# 11_iMX_8X_SPI_ADC.net
KiCad netlist of a schematic drawn in Altium Designer
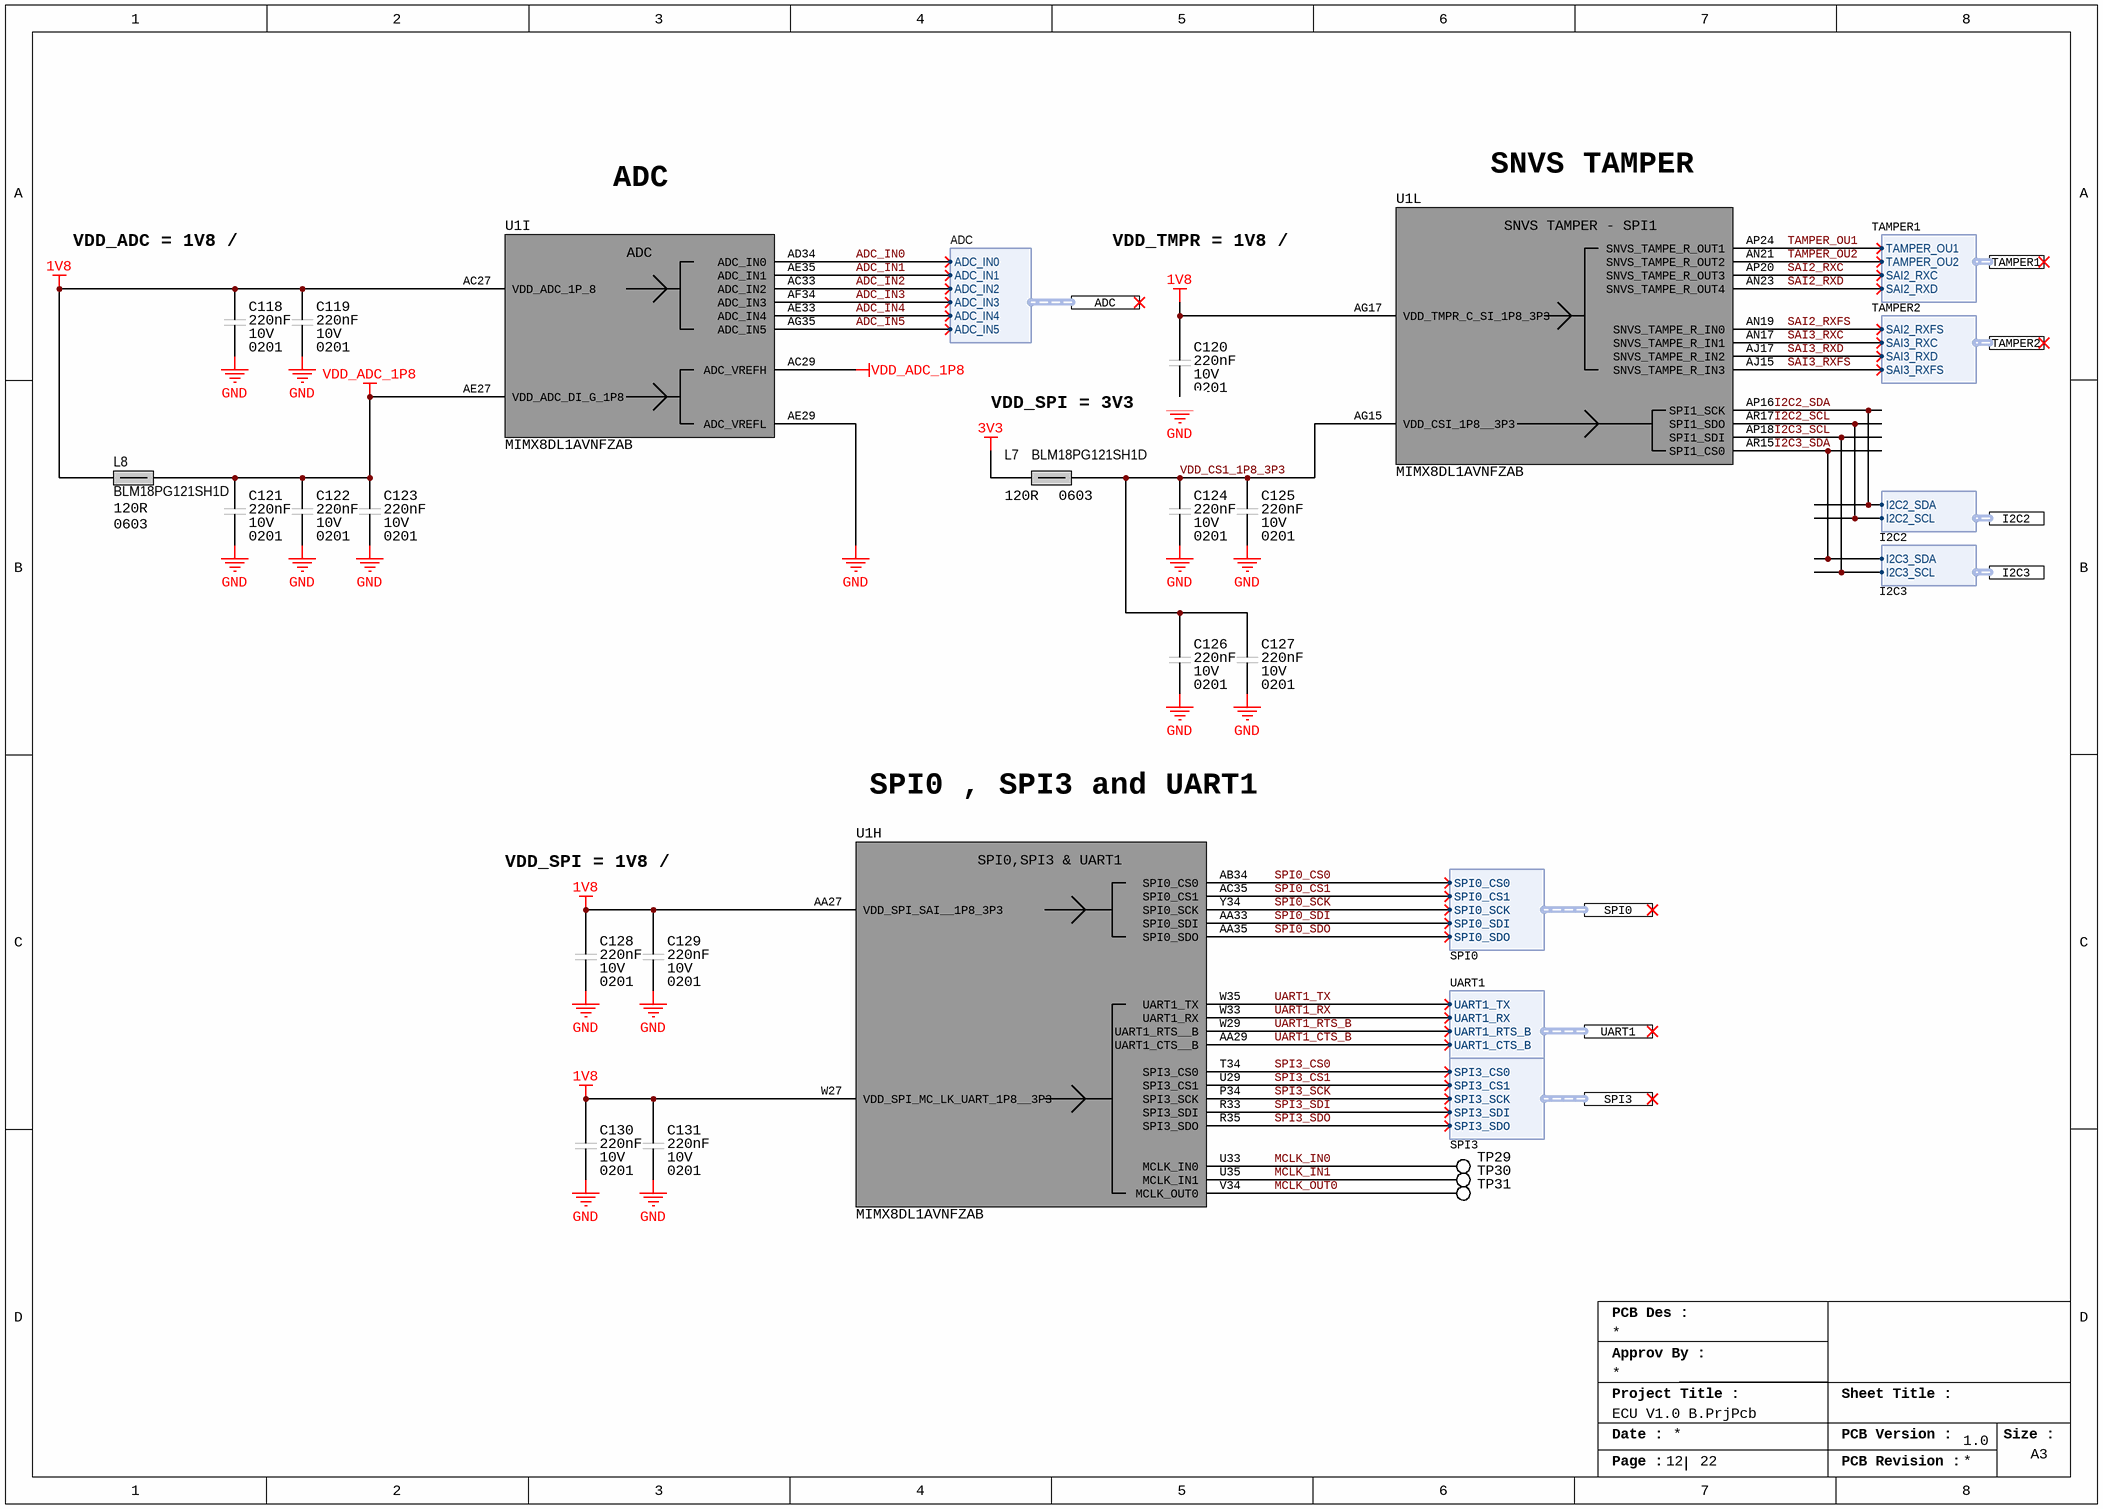
[diagram p0: 11_iMX 8X_SPI & ADC.SchDoc]

(export (version "E")
  (design (tool "Eeschema 10.0.6"))
  (components
    (comp (ref "C118")
      (value "LMK063BJ224MP-F")
      (footprint "CAP_0201_CAPC0603X03N")
      (description "Multilayer Ceramic Capacitors (High dielectric type), 10V, 0.22 uF, ± 20 %, 0201, X5R, RoHS")
      (fields
        (field (name "MANUFACTURER") "Taiyo Yuden")
        (field (name "TOLERANCE") "20%")
        (field (name "VOLTAGE RATING (DC)") "10V")
        (field (name "CAPACITANCE") "220nF")
        (field (name "CASE/PACKAGE") "0201")
      )
      (libsource (lib "Electronic Devices_LIB") (part "CAP_0.22UF_10V_X5R_0201"))
    )
    (comp (ref "C119")
      (value "LMK063BJ224MP-F")
      (footprint "CAP_0201_CAPC0603X03N")
      (description "Multilayer Ceramic Capacitors (High dielectric type), 10V, 0.22 uF, ± 20 %, 0201, X5R, RoHS")
      (fields
        (field (name "MANUFACTURER") "Taiyo Yuden")
        (field (name "TOLERANCE") "20%")
        (field (name "VOLTAGE RATING (DC)") "10V")
        (field (name "CAPACITANCE") "220nF")
        (field (name "CASE/PACKAGE") "0201")
      )
      (libsource (lib "Electronic Devices_LIB") (part "CAP_0.22UF_10V_X5R_0201"))
    )
    (comp (ref "C120")
      (value "LMK063BJ224MP-F")
      (footprint "CAP_0201_CAPC0603X03N")
      (description "Multilayer Ceramic Capacitors (High dielectric type), 10V, 0.22 uF, ± 20 %, 0201, X5R, RoHS")
      (fields
        (field (name "MANUFACTURER") "Taiyo Yuden")
        (field (name "TOLERANCE") "20%")
        (field (name "VOLTAGE RATING (DC)") "10V")
        (field (name "CAPACITANCE") "220nF")
        (field (name "CASE/PACKAGE") "0201")
      )
      (libsource (lib "Electronic Devices_LIB") (part "CAP_0.22UF_10V_X5R_0201"))
    )
    (comp (ref "C121")
      (value "LMK063BJ224MP-F")
      (footprint "CAP_0201_CAPC0603X03N")
      (description "Multilayer Ceramic Capacitors (High dielectric type), 10V, 0.22 uF, ± 20 %, 0201, X5R, RoHS")
      (fields
        (field (name "MANUFACTURER") "Taiyo Yuden")
        (field (name "TOLERANCE") "20%")
        (field (name "VOLTAGE RATING (DC)") "10V")
        (field (name "CAPACITANCE") "220nF")
        (field (name "CASE/PACKAGE") "0201")
      )
      (libsource (lib "Electronic Devices_LIB") (part "CAP_0.22UF_10V_X5R_0201"))
    )
    (comp (ref "C122")
      (value "LMK063BJ224MP-F")
      (footprint "CAP_0201_CAPC0603X03N")
      (description "Multilayer Ceramic Capacitors (High dielectric type), 10V, 0.22 uF, ± 20 %, 0201, X5R, RoHS")
      (fields
        (field (name "MANUFACTURER") "Taiyo Yuden")
        (field (name "TOLERANCE") "20%")
        (field (name "VOLTAGE RATING (DC)") "10V")
        (field (name "CAPACITANCE") "220nF")
        (field (name "CASE/PACKAGE") "0201")
      )
      (libsource (lib "Electronic Devices_LIB") (part "CAP_0.22UF_10V_X5R_0201"))
    )
    (comp (ref "C123")
      (value "LMK063BJ224MP-F")
      (footprint "CAP_0201_CAPC0603X03N")
      (description "Multilayer Ceramic Capacitors (High dielectric type), 10V, 0.22 uF, ± 20 %, 0201, X5R, RoHS")
      (fields
        (field (name "MANUFACTURER") "Taiyo Yuden")
        (field (name "TOLERANCE") "20%")
        (field (name "VOLTAGE RATING (DC)") "10V")
        (field (name "CAPACITANCE") "220nF")
        (field (name "CASE/PACKAGE") "0201")
      )
      (libsource (lib "Electronic Devices_LIB") (part "CAP_0.22UF_10V_X5R_0201"))
    )
    (comp (ref "C124")
      (value "LMK063BJ224MP-F")
      (footprint "CAP_0201_CAPC0603X03N")
      (description "Multilayer Ceramic Capacitors (High dielectric type), 10V, 0.22 uF, ± 20 %, 0201, X5R, RoHS")
      (fields
        (field (name "MANUFACTURER") "Taiyo Yuden")
        (field (name "TOLERANCE") "20%")
        (field (name "VOLTAGE RATING (DC)") "10V")
        (field (name "CAPACITANCE") "220nF")
        (field (name "CASE/PACKAGE") "0201")
      )
      (libsource (lib "Electronic Devices_LIB") (part "CAP_0.22UF_10V_X5R_0201"))
    )
    (comp (ref "C125")
      (value "LMK063BJ224MP-F")
      (footprint "CAP_0201_CAPC0603X03N")
      (description "Multilayer Ceramic Capacitors (High dielectric type), 10V, 0.22 uF, ± 20 %, 0201, X5R, RoHS")
      (fields
        (field (name "MANUFACTURER") "Taiyo Yuden")
        (field (name "TOLERANCE") "20%")
        (field (name "VOLTAGE RATING (DC)") "10V")
        (field (name "CAPACITANCE") "220nF")
        (field (name "CASE/PACKAGE") "0201")
      )
      (libsource (lib "Electronic Devices_LIB") (part "CAP_0.22UF_10V_X5R_0201"))
    )
    (comp (ref "C126")
      (value "LMK063BJ224MP-F")
      (footprint "CAP_0201_CAPC0603X03N")
      (description "Multilayer Ceramic Capacitors (High dielectric type), 10V, 0.22 uF, ± 20 %, 0201, X5R, RoHS")
      (fields
        (field (name "MANUFACTURER") "Taiyo Yuden")
        (field (name "TOLERANCE") "20%")
        (field (name "VOLTAGE RATING (DC)") "10V")
        (field (name "CAPACITANCE") "220nF")
        (field (name "CASE/PACKAGE") "0201")
      )
      (libsource (lib "Electronic Devices_LIB") (part "CAP_0.22UF_10V_X5R_0201"))
    )
    (comp (ref "C127")
      (value "LMK063BJ224MP-F")
      (footprint "CAP_0201_CAPC0603X03N")
      (description "Multilayer Ceramic Capacitors (High dielectric type), 10V, 0.22 uF, ± 20 %, 0201, X5R, RoHS")
      (fields
        (field (name "MANUFACTURER") "Taiyo Yuden")
        (field (name "TOLERANCE") "20%")
        (field (name "VOLTAGE RATING (DC)") "10V")
        (field (name "CAPACITANCE") "220nF")
        (field (name "CASE/PACKAGE") "0201")
      )
      (libsource (lib "Electronic Devices_LIB") (part "CAP_0.22UF_10V_X5R_0201"))
    )
    (comp (ref "C128")
      (value "LMK063BJ224MP-F")
      (footprint "CAP_0201_CAPC0603X03N")
      (description "Multilayer Ceramic Capacitors (High dielectric type), 10V, 0.22 uF, ± 20 %, 0201, X5R, RoHS")
      (fields
        (field (name "MANUFACTURER") "Taiyo Yuden")
        (field (name "TOLERANCE") "20%")
        (field (name "VOLTAGE RATING (DC)") "10V")
        (field (name "CAPACITANCE") "220nF")
        (field (name "CASE/PACKAGE") "0201")
      )
      (libsource (lib "Electronic Devices_LIB") (part "CAP_0.22UF_10V_X5R_0201"))
    )
    (comp (ref "C129")
      (value "LMK063BJ224MP-F")
      (footprint "CAP_0201_CAPC0603X03N")
      (description "Multilayer Ceramic Capacitors (High dielectric type), 10V, 0.22 uF, ± 20 %, 0201, X5R, RoHS")
      (fields
        (field (name "MANUFACTURER") "Taiyo Yuden")
        (field (name "TOLERANCE") "20%")
        (field (name "VOLTAGE RATING (DC)") "10V")
        (field (name "CAPACITANCE") "220nF")
        (field (name "CASE/PACKAGE") "0201")
      )
      (libsource (lib "Electronic Devices_LIB") (part "CAP_0.22UF_10V_X5R_0201"))
    )
    (comp (ref "C130")
      (value "LMK063BJ224MP-F")
      (footprint "CAP_0201_CAPC0603X03N")
      (description "Multilayer Ceramic Capacitors (High dielectric type), 10V, 0.22 uF, ± 20 %, 0201, X5R, RoHS")
      (fields
        (field (name "MANUFACTURER") "Taiyo Yuden")
        (field (name "TOLERANCE") "20%")
        (field (name "VOLTAGE RATING (DC)") "10V")
        (field (name "CAPACITANCE") "220nF")
        (field (name "CASE/PACKAGE") "0201")
      )
      (libsource (lib "Electronic Devices_LIB") (part "CAP_0.22UF_10V_X5R_0201"))
    )
    (comp (ref "C131")
      (value "LMK063BJ224MP-F")
      (footprint "CAP_0201_CAPC0603X03N")
      (description "Multilayer Ceramic Capacitors (High dielectric type), 10V, 0.22 uF, ± 20 %, 0201, X5R, RoHS")
      (fields
        (field (name "MANUFACTURER") "Taiyo Yuden")
        (field (name "TOLERANCE") "20%")
        (field (name "VOLTAGE RATING (DC)") "10V")
        (field (name "CAPACITANCE") "220nF")
        (field (name "CASE/PACKAGE") "0201")
      )
      (libsource (lib "Electronic Devices_LIB") (part "CAP_0.22UF_10V_X5R_0201"))
    )
    (comp (ref "L7")
      (value "BLM18PG121SH1D")
      (footprint "IND_0603_INDC1608X08N")
      (description "Ferrite Beads Multi-Layer 120Ohm 25% 100MHz 2A 50mOhm DCR 0603 Automotive Paper T/R")
      (fields
        (field (name "MANUFACTURER") "Murata")
        (field (name "TOLERANCE") "25%")
        (field (name "IMPEDANCE") "120R")
        (field (name "CASE/PACKAGE") "0603")
      )
      (libsource (lib "Electronic Devices_LIB") (part "IND_FERRITE_BEADS_120R_2A_0603_BLM18PG121SH1D"))
    )
    (comp (ref "L8")
      (value "BLM18PG121SH1D")
      (footprint "IND_0603_INDC1608X08N")
      (description "Ferrite Beads Multi-Layer 120Ohm 25% 100MHz 2A 50mOhm DCR 0603 Automotive Paper T/R")
      (fields
        (field (name "MANUFACTURER") "Murata")
        (field (name "TOLERANCE") "25%")
        (field (name "IMPEDANCE") "120R")
        (field (name "CASE/PACKAGE") "0603")
      )
      (libsource (lib "Electronic Devices_LIB") (part "IND_FERRITE_BEADS_120R_2A_0603_BLM18PG121SH1D"))
    )
    (comp (ref "TP29")
      (value "NO COMPONENT")
      (footprint "TP_PAD_0.5MM_SMD_ROUND")
      (description "Test Point, SMD pad, round, 1.5mm, 1.6mm, 3mm diameter")
      (libsource (lib "Electronic Devices_LIB") (part "TP_PAD_SMD_SMALL"))
    )
    (comp (ref "TP30")
      (value "NO COMPONENT")
      (footprint "TP_PAD_0.5MM_SMD_ROUND")
      (description "Test Point, SMD pad, round, 1.5mm, 1.6mm, 3mm diameter")
      (libsource (lib "Electronic Devices_LIB") (part "TP_PAD_SMD_SMALL"))
    )
    (comp (ref "TP31")
      (value "NO COMPONENT")
      (footprint "TP_PAD_0.5MM_SMD_ROUND")
      (description "Test Point, SMD pad, round, 1.5mm, 1.6mm, 3mm diameter")
      (libsource (lib "Electronic Devices_LIB") (part "TP_PAD_SMD_SMALL"))
    )
    (comp (ref "U1")
      (value "MIMX8DL1AVNFZAB")
      (footprint "MIMX8DL1AVNFZAB")
      (description "I.MX8 Dxl 15SQ / Tray Rohs Compliant: Yes")
      (fields (field (name "MANUFACTURER") "NXP Semiconductors"))
      (libsource (lib "Electronic Devices_LIB") (part "IC_MPU_ARM_1.2GHz_MIMX8DL1AVNFZAB"))
    )
  )
  (nets
    (net (code "9") (name "/ADC_IN0") (class "Default")
      (node (ref "U1") (pin "AD34") (pinfunction "ADC_IN0_AD34") (pintype "passive+no_connect"))
    )
    (net (code "10") (name "/ADC_IN1") (class "Default")
      (node (ref "U1") (pin "AE35") (pinfunction "ADC_IN1_AE35") (pintype "passive+no_connect"))
    )
    (net (code "11") (name "/ADC_IN2") (class "Default")
      (node (ref "U1") (pin "AC33") (pinfunction "ADC_IN2_AC33") (pintype "passive+no_connect"))
    )
    (net (code "12") (name "/ADC_IN3") (class "Default")
      (node (ref "U1") (pin "AF34") (pinfunction "ADC_IN3_AF34") (pintype "passive+no_connect"))
    )
    (net (code "13") (name "/ADC_IN4") (class "Default")
      (node (ref "U1") (pin "AE33") (pinfunction "ADC_IN4_AE33") (pintype "passive+no_connect"))
    )
    (net (code "14") (name "/ADC_IN5") (class "Default")
      (node (ref "U1") (pin "AG35") (pinfunction "ADC_IN5_AG35") (pintype "passive+no_connect"))
    )
    (net (code "15") (name "/I2C2_SCL") (class "Default")
      (node (ref "U1") (pin "AR17") (pinfunction "SPI1_SDO_AR17") (pintype "passive"))
    )
    (net (code "16") (name "/I2C2_SDA") (class "Default")
      (node (ref "U1") (pin "AP16") (pinfunction "SPI1_SCK_AP16") (pintype "passive"))
    )
    (net (code "17") (name "/I2C3_SCL") (class "Default")
      (node (ref "U1") (pin "AP18") (pinfunction "SPI1_SDI_AP18") (pintype "passive"))
    )
    (net (code "18") (name "/I2C3_SDA") (class "Default")
      (node (ref "U1") (pin "AR15") (pinfunction "SPI1_CS0_AR15") (pintype "passive"))
    )
    (net (code "19") (name "/MCLK_IN0") (class "Default")
      (node (ref "TP29") (pin "1") (pinfunction "1_1") (pintype "passive"))
      (node (ref "U1") (pin "U33") (pinfunction "MCLK_IN0_U33") (pintype "passive"))
    )
    (net (code "20") (name "/MCLK_IN1") (class "Default")
      (node (ref "TP30") (pin "1") (pinfunction "1_1") (pintype "passive"))
      (node (ref "U1") (pin "U35") (pinfunction "MCLK_IN1_U35") (pintype "passive"))
    )
    (net (code "21") (name "/MCLK_OUT0") (class "Default")
      (node (ref "TP31") (pin "1") (pinfunction "1_1") (pintype "passive"))
      (node (ref "U1") (pin "V34") (pinfunction "MCLK_OUT0_V34") (pintype "passive"))
    )
    (net (code "22") (name "/SAI2_RXC") (class "Default")
      (node (ref "U1") (pin "AP20") (pinfunction "SNVS_TAMPE_R_OUT3_AP20") (pintype "passive+no_connect"))
    )
    (net (code "23") (name "/SAI2_RXD") (class "Default")
      (node (ref "U1") (pin "AN23") (pinfunction "SNVS_TAMPE_R_OUT4_AN23") (pintype "passive+no_connect"))
    )
    (net (code "24") (name "/SAI2_RXFS") (class "Default")
      (node (ref "U1") (pin "AN19") (pinfunction "SNVS_TAMPE_R_IN0_AN19") (pintype "passive+no_connect"))
    )
    (net (code "25") (name "/SAI3_RXC") (class "Default")
      (node (ref "U1") (pin "AN17") (pinfunction "SNVS_TAMPE_R_IN1_AN17") (pintype "passive+no_connect"))
    )
    (net (code "26") (name "/SAI3_RXD") (class "Default")
      (node (ref "U1") (pin "AJ17") (pinfunction "SNVS_TAMPE_R_IN2_AJ17") (pintype "passive+no_connect"))
    )
    (net (code "27") (name "/SAI3_RXFS") (class "Default")
      (node (ref "U1") (pin "AJ15") (pinfunction "SNVS_TAMPE_R_IN3_AJ15") (pintype "passive+no_connect"))
    )
    (net (code "28") (name "/SPI0_CS0") (class "Default")
      (node (ref "U1") (pin "AB34") (pinfunction "SPI0_CS0_AB34") (pintype "passive+no_connect"))
    )
    (net (code "29") (name "/SPI0_CS1") (class "Default")
      (node (ref "U1") (pin "AC35") (pinfunction "SPI0_CS1_AC35") (pintype "passive+no_connect"))
    )
    (net (code "30") (name "/SPI0_SCK") (class "Default")
      (node (ref "U1") (pin "Y34") (pinfunction "SPI0_SCK_Y34") (pintype "passive+no_connect"))
    )
    (net (code "31") (name "/SPI0_SDI") (class "Default")
      (node (ref "U1") (pin "AA33") (pinfunction "SPI0_SDI_AA33") (pintype "passive+no_connect"))
    )
    (net (code "32") (name "/SPI0_SDO") (class "Default")
      (node (ref "U1") (pin "AA35") (pinfunction "SPI0_SDO_AA35") (pintype "passive+no_connect"))
    )
    (net (code "33") (name "/SPI3_CS0") (class "Default")
      (node (ref "U1") (pin "T34") (pinfunction "SPI3_CS0_T34") (pintype "passive+no_connect"))
    )
    (net (code "34") (name "/SPI3_CS1") (class "Default")
      (node (ref "U1") (pin "U29") (pinfunction "SPI3_CS1_U29") (pintype "passive+no_connect"))
    )
    (net (code "35") (name "/SPI3_SCK") (class "Default")
      (node (ref "U1") (pin "P34") (pinfunction "SPI3_SCK_P34") (pintype "passive+no_connect"))
    )
    (net (code "36") (name "/SPI3_SDI") (class "Default")
      (node (ref "U1") (pin "R33") (pinfunction "SPI3_SDI_R33") (pintype "passive+no_connect"))
    )
    (net (code "37") (name "/SPI3_SDO") (class "Default")
      (node (ref "U1") (pin "R35") (pinfunction "SPI3_SDO_R35") (pintype "passive+no_connect"))
    )
    (net (code "38") (name "/TAMPER_OU1") (class "Default")
      (node (ref "U1") (pin "AP24") (pinfunction "SNVS_TAMPE_R_OUT1_AP24") (pintype "passive+no_connect"))
    )
    (net (code "39") (name "/TAMPER_OU2") (class "Default")
      (node (ref "U1") (pin "AN21") (pinfunction "SNVS_TAMPE_R_OUT2_AN21") (pintype "passive+no_connect"))
    )
    (net (code "40") (name "/UART1_CTS_B") (class "Default")
      (node (ref "U1") (pin "AA29") (pinfunction "UART1_CTS__B_AA29") (pintype "passive+no_connect"))
    )
    (net (code "41") (name "/UART1_RTS_B") (class "Default")
      (node (ref "U1") (pin "W29") (pinfunction "UART1_RTS__B_W29") (pintype "passive+no_connect"))
    )
    (net (code "42") (name "/UART1_RX") (class "Default")
      (node (ref "U1") (pin "W33") (pinfunction "UART1_RX_W33") (pintype "passive+no_connect"))
    )
    (net (code "43") (name "/UART1_TX") (class "Default")
      (node (ref "U1") (pin "W35") (pinfunction "UART1_TX_W35") (pintype "passive+no_connect"))
    )
    (net (code "45") (name "/VDD_CS1_1P8_3P3") (class "Default")
      (node (ref "C124") (pin "2") (pinfunction "2_2") (pintype "passive"))
      (node (ref "C125") (pin "2") (pinfunction "2_2") (pintype "passive"))
      (node (ref "C126") (pin "2") (pinfunction "2_2") (pintype "passive"))
      (node (ref "C127") (pin "2") (pinfunction "2_2") (pintype "passive"))
      (node (ref "L7") (pin "2") (pinfunction "2_2") (pintype "passive"))
      (node (ref "U1") (pin "AG15") (pinfunction "VDD_CSI_1P8__3P3_AG15") (pintype "passive"))
    )
    (net (code "53") (name "1V8") (class "Default")
      (node (ref "C118") (pin "2") (pinfunction "2_2") (pintype "passive"))
      (node (ref "C119") (pin "2") (pinfunction "2_2") (pintype "passive"))
      (node (ref "C120") (pin "2") (pinfunction "2_2") (pintype "passive"))
      (node (ref "C128") (pin "2") (pinfunction "2_2") (pintype "passive"))
      (node (ref "C129") (pin "2") (pinfunction "2_2") (pintype "passive"))
      (node (ref "C130") (pin "2") (pinfunction "2_2") (pintype "passive"))
      (node (ref "C131") (pin "2") (pinfunction "2_2") (pintype "passive"))
      (node (ref "L8") (pin "1") (pinfunction "1_1") (pintype "passive"))
      (node (ref "U1") (pin "AA27") (pinfunction "VDD_SPI_SAI__1P8_3P3_AA27") (pintype "passive"))
      (node (ref "U1") (pin "AC27") (pinfunction "VDD_ADC_1P_8_AC27") (pintype "passive"))
      (node (ref "U1") (pin "AG17") (pinfunction "VDD_TMPR_C_SI_1P8_3P3_AG17") (pintype "passive"))
      (node (ref "U1") (pin "W27") (pinfunction "VDD_SPI_MC_LK_UART_1P8__3P3_W27") (pintype "passive"))
    )
    (net (code "54") (name "3V3") (class "Default")
      (node (ref "L7") (pin "1") (pinfunction "1_1") (pintype "passive"))
    )
    (net (code "55") (name "GND") (class "Default")
      (node (ref "C118") (pin "1") (pinfunction "1_1") (pintype "passive"))
      (node (ref "C119") (pin "1") (pinfunction "1_1") (pintype "passive"))
      (node (ref "C120") (pin "1") (pinfunction "1_1") (pintype "passive"))
      (node (ref "C121") (pin "1") (pinfunction "1_1") (pintype "passive"))
      (node (ref "C122") (pin "1") (pinfunction "1_1") (pintype "passive"))
      (node (ref "C123") (pin "1") (pinfunction "1_1") (pintype "passive"))
      (node (ref "C124") (pin "1") (pinfunction "1_1") (pintype "passive"))
      (node (ref "C125") (pin "1") (pinfunction "1_1") (pintype "passive"))
      (node (ref "C126") (pin "1") (pinfunction "1_1") (pintype "passive"))
      (node (ref "C127") (pin "1") (pinfunction "1_1") (pintype "passive"))
      (node (ref "C128") (pin "1") (pinfunction "1_1") (pintype "passive"))
      (node (ref "C129") (pin "1") (pinfunction "1_1") (pintype "passive"))
      (node (ref "C130") (pin "1") (pinfunction "1_1") (pintype "passive"))
      (node (ref "C131") (pin "1") (pinfunction "1_1") (pintype "passive"))
      (node (ref "U1") (pin "AE29") (pinfunction "ADC_VREFL_AE29") (pintype "passive"))
    )
    (net (code "56") (name "VDD_ADC_1P8") (class "Default")
      (node (ref "C121") (pin "2") (pinfunction "2_2") (pintype "passive"))
      (node (ref "C122") (pin "2") (pinfunction "2_2") (pintype "passive"))
      (node (ref "C123") (pin "2") (pinfunction "2_2") (pintype "passive"))
      (node (ref "L8") (pin "2") (pinfunction "2_2") (pintype "passive"))
      (node (ref "U1") (pin "AC29") (pinfunction "ADC_VREFH_AC29") (pintype "passive"))
      (node (ref "U1") (pin "AE27") (pinfunction "VDD_ADC_DI_G_1P8_AE27") (pintype "passive"))
    )
  )
)
